# Moway_IR.net
KiCad netlist of a schematic drawn in Altium Designer
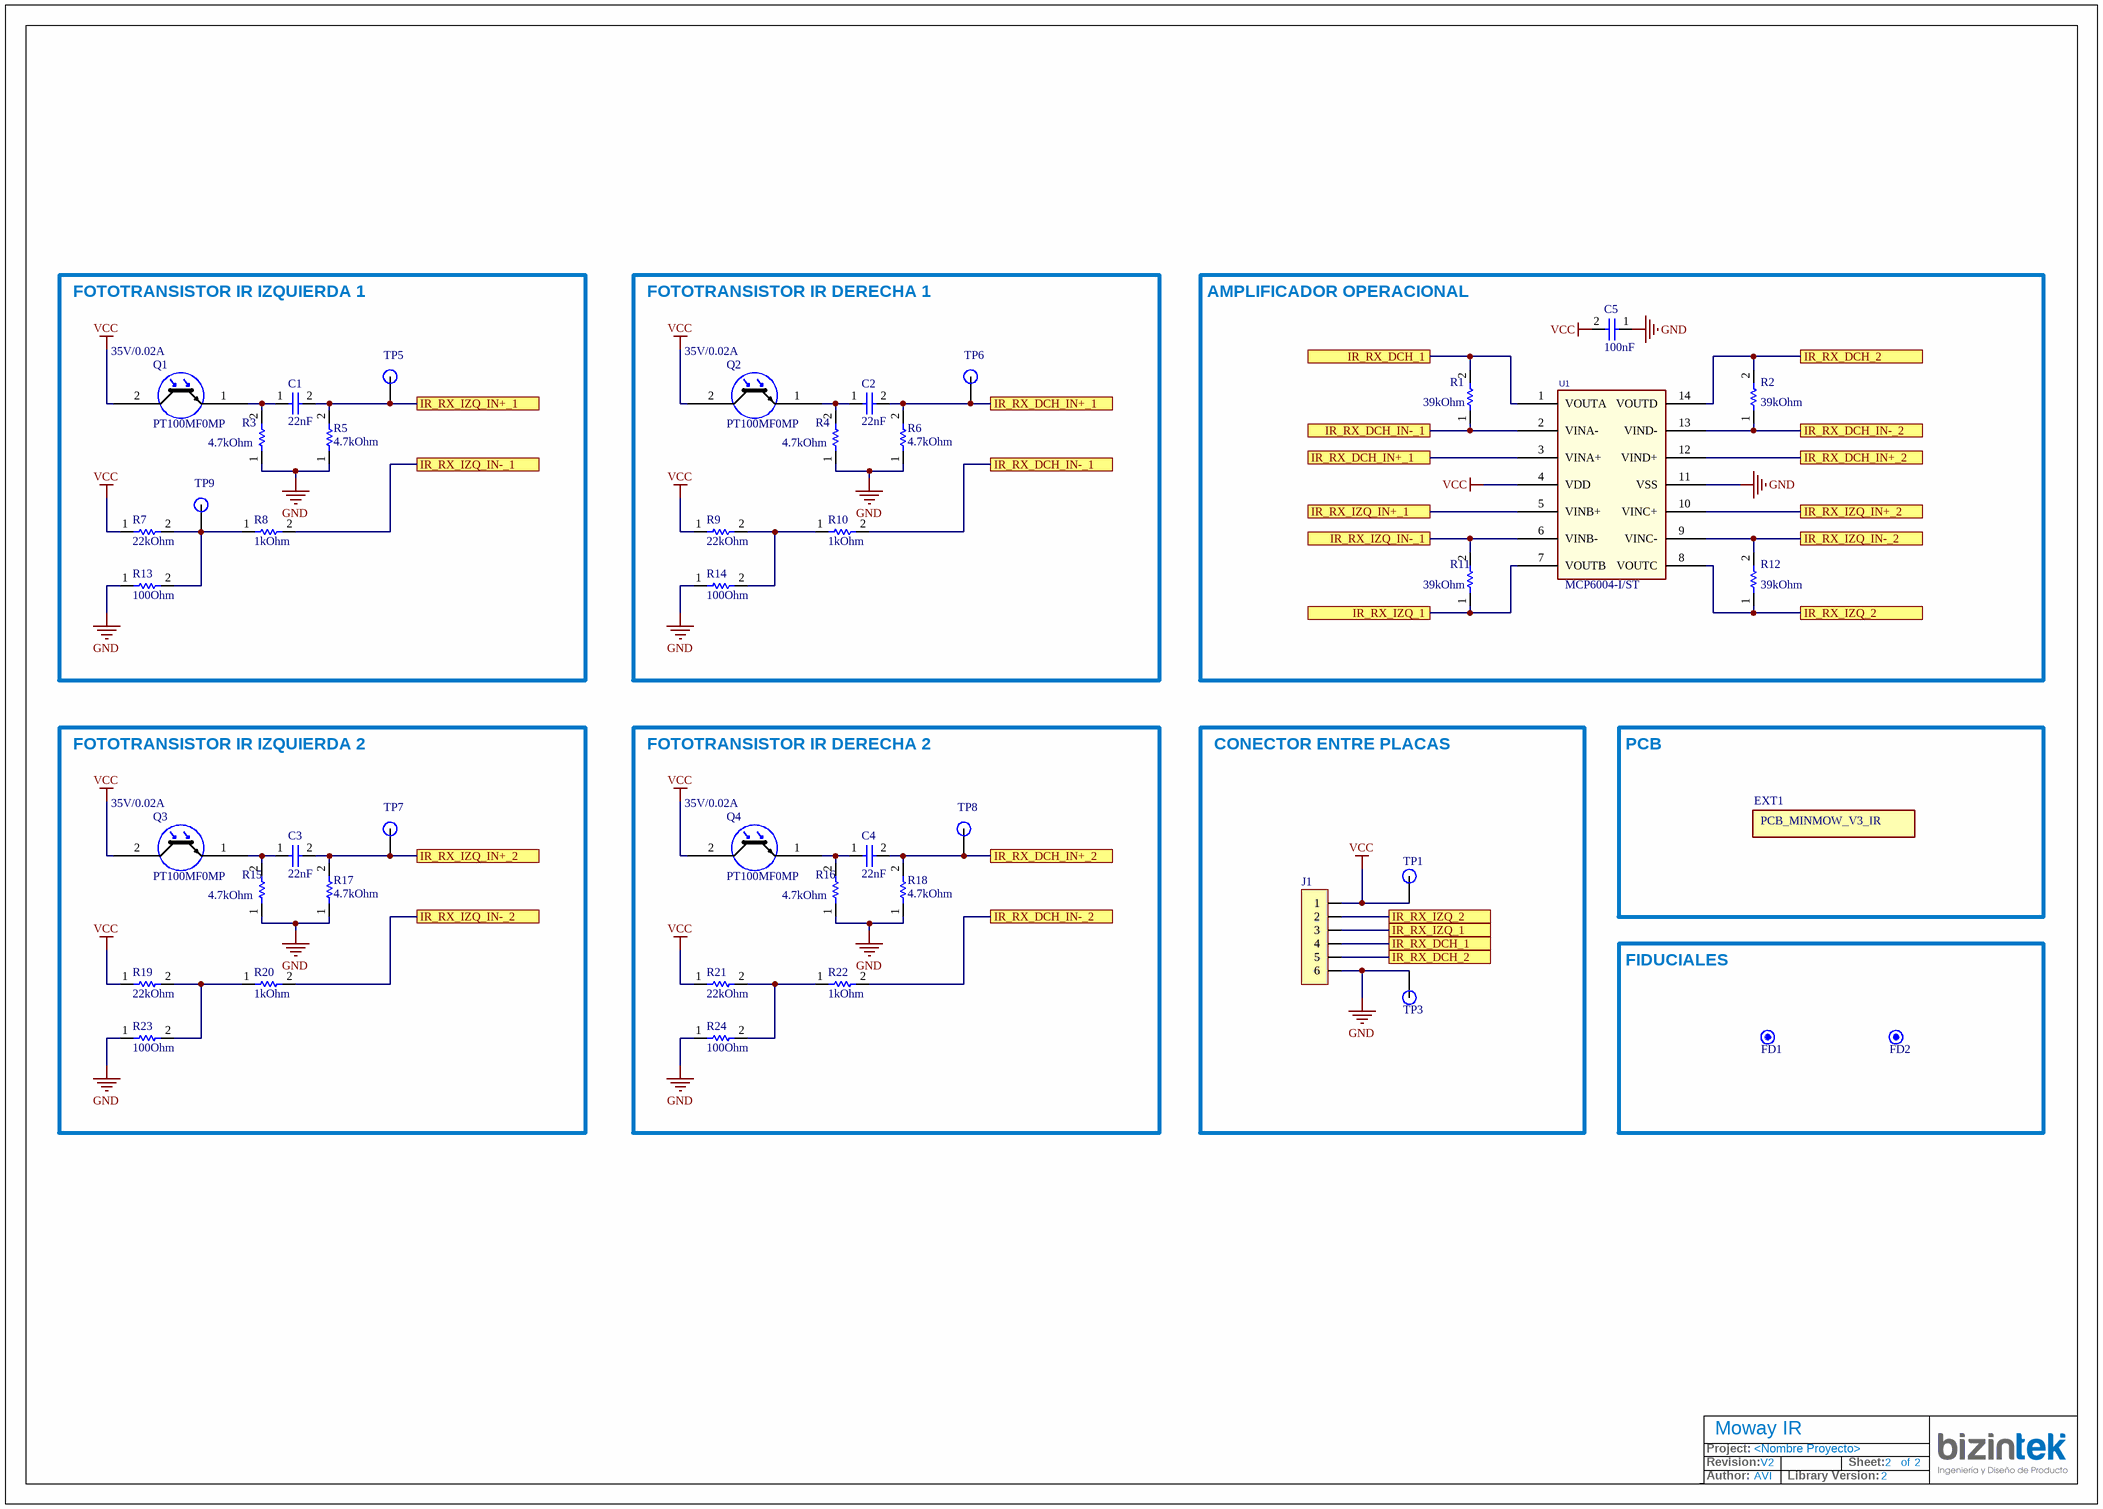
[diagram p0: Moway IR.SchDoc]

(export (version "E")
  (design (tool "Eeschema 10.0.6"))
  (components
    (comp (ref "C1")
      (value "22nF")
      (footprint "C0603")
      (description "CAPACITOR SMD 0603, 22nF , 10V, X7R")
      (fields (field (name "PART NUMBER") "C22NV10X7R0603") (field (name "VOLTAGE") "10"))
      (libsource (lib "BZI_ALTIUMLIB") (part "CAPACITOR"))
    )
    (comp (ref "C2")
      (value "22nF")
      (footprint "C0603")
      (description "CAPACITOR SMD 0603, 22nF , 10V, X7R")
      (fields (field (name "PART NUMBER") "C22NV10X7R0603") (field (name "VOLTAGE") "10"))
      (libsource (lib "BZI_ALTIUMLIB") (part "CAPACITOR"))
    )
    (comp (ref "C3")
      (value "22nF")
      (footprint "C0603")
      (description "CAPACITOR SMD 0603, 22nF , 10V, X7R")
      (fields (field (name "PART NUMBER") "C22NV10X7R0603") (field (name "VOLTAGE") "10"))
      (libsource (lib "BZI_ALTIUMLIB") (part "CAPACITOR"))
    )
    (comp (ref "C4")
      (value "22nF")
      (footprint "C0603")
      (description "CAPACITOR SMD 0603, 22nF , 10V, X7R")
      (fields (field (name "PART NUMBER") "C22NV10X7R0603") (field (name "VOLTAGE") "10"))
      (libsource (lib "BZI_ALTIUMLIB") (part "CAPACITOR"))
    )
    (comp (ref "C5")
      (value "100nF")
      (footprint "C0603")
      (description "CAPACITOR SMD 0603, 100nF, 10V, X7R")
      (fields (field (name "PART NUMBER") "C100NV10X7R0603") (field (name "VOLTAGE") "10"))
      (libsource (lib "BZI_ALTIUMLIB") (part "CAPACITOR"))
    )
    (comp (ref "EXT1")
      (value "PCB_MINMOW_V3_IR")
      (fields
        (field (name "PART NUMBER") "PCB")
        (field (name "MANUFACTURER") "BIZINTEK")
        (field (name "MANUFACTURER PART NUMBER") "PCB_MINMOW_V2_IR")
      )
      (libsource (lib "BZI_ALTIUMLIB") (part "EXTERNAL_GEN"))
    )
    (comp (ref "FD1")
      (value "FIDUCIAL")
      (footprint "FIDUCIAL")
      (libsource (lib "BZI_ALTIUMLIB") (part "FIDUCIAL"))
    )
    (comp (ref "FD2")
      (value "FIDUCIAL")
      (footprint "FIDUCIAL")
      (libsource (lib "BZI_ALTIUMLIB") (part "FIDUCIAL"))
    )
    (comp (ref "J1")
      (value "PAD_6PIN_3X2_1.05MM_1.27MM_PITCH")
      (footprint "PAD_6PIN_3X2_1.05MM_1.27MM_PITCH")
      (libsource (lib "BZI_ALTIUMLIB") (part "HEADER_6PIN"))
    )
    (comp (ref "Q1")
      (value "35V/0.02A")
      (footprint "PT100MF0MP_SIDE")
      (description "SMT Phototransistor, 15º angle, 910nm, 3.45mA (SIDE MOUNTING)")
      (fields
        (field (name "PART NUMBER") "PT100MF0MP_S")
        (field (name "MANUFACTURER PART NUMBER") "PT100MF0MP")
        (field (name "MANUFACTURER") "SHARP")
      )
      (libsource (lib "BZI_ALTIUMLIB") (part "PHOTOTRANSISTOR_BJT"))
    )
    (comp (ref "Q2")
      (value "35V/0.02A")
      (footprint "PT100MF0MP_SIDE")
      (description "SMT Phototransistor, 15º angle, 910nm, 3.45mA (SIDE MOUNTING)")
      (fields
        (field (name "PART NUMBER") "PT100MF0MP_S")
        (field (name "MANUFACTURER PART NUMBER") "PT100MF0MP")
        (field (name "MANUFACTURER") "SHARP")
      )
      (libsource (lib "BZI_ALTIUMLIB") (part "PHOTOTRANSISTOR_BJT"))
    )
    (comp (ref "Q3")
      (value "35V/0.02A")
      (footprint "PT100MF0MP_SIDE")
      (description "SMT Phototransistor, 15º angle, 910nm, 3.45mA (SIDE MOUNTING)")
      (fields
        (field (name "PART NUMBER") "PT100MF0MP_S")
        (field (name "MANUFACTURER PART NUMBER") "PT100MF0MP")
        (field (name "MANUFACTURER") "SHARP")
      )
      (libsource (lib "BZI_ALTIUMLIB") (part "PHOTOTRANSISTOR_BJT"))
    )
    (comp (ref "Q4")
      (value "35V/0.02A")
      (footprint "PT100MF0MP_SIDE")
      (description "SMT Phototransistor, 15º angle, 910nm, 3.45mA (SIDE MOUNTING)")
      (fields
        (field (name "PART NUMBER") "PT100MF0MP_S")
        (field (name "MANUFACTURER PART NUMBER") "PT100MF0MP")
        (field (name "MANUFACTURER") "SHARP")
      )
      (libsource (lib "BZI_ALTIUMLIB") (part "PHOTOTRANSISTOR_BJT"))
    )
    (comp (ref "R1")
      (value "39kOhm")
      (footprint "R0402")
      (description "RESISTOR SMD 0402, 39kOhm, 1%")
      (fields (field (name "PART NUMBER") "R39KT10402") (field (name "TOLERANCE") "1"))
      (libsource (lib "BZI_ALTIUMLIB") (part "RESISTOR"))
    )
    (comp (ref "R2")
      (value "39kOhm")
      (footprint "R0402")
      (description "RESISTOR SMD 0402, 39kOhm, 1%")
      (fields (field (name "PART NUMBER") "R39KT10402") (field (name "TOLERANCE") "1"))
      (libsource (lib "BZI_ALTIUMLIB") (part "RESISTOR"))
    )
    (comp (ref "R3")
      (value "4.7kOhm")
      (footprint "R0402")
      (description "RESISTOR SMD 0402, 4.7kOhm, 1%")
      (fields (field (name "PART NUMBER") "R4K7T10402") (field (name "TOLERANCE") "1"))
      (libsource (lib "BZI_ALTIUMLIB") (part "RESISTOR"))
    )
    (comp (ref "R4")
      (value "4.7kOhm")
      (footprint "R0402")
      (description "RESISTOR SMD 0402, 4.7kOhm, 1%")
      (fields (field (name "PART NUMBER") "R4K7T10402") (field (name "TOLERANCE") "1"))
      (libsource (lib "BZI_ALTIUMLIB") (part "RESISTOR"))
    )
    (comp (ref "R5")
      (value "4.7kOhm")
      (footprint "R0402")
      (description "RESISTOR SMD 0402, 4.7kOhm, 1%")
      (fields (field (name "PART NUMBER") "R4K7T10402") (field (name "TOLERANCE") "1"))
      (libsource (lib "BZI_ALTIUMLIB") (part "RESISTOR"))
    )
    (comp (ref "R6")
      (value "4.7kOhm")
      (footprint "R0402")
      (description "RESISTOR SMD 0402, 4.7kOhm, 1%")
      (fields (field (name "PART NUMBER") "R4K7T10402") (field (name "TOLERANCE") "1"))
      (libsource (lib "BZI_ALTIUMLIB") (part "RESISTOR"))
    )
    (comp (ref "R7")
      (value "22kOhm")
      (footprint "R0402")
      (description "RESISTOR SMD 0402, 22kOhm, 1%")
      (fields (field (name "PART NUMBER") "R22KT10402") (field (name "TOLERANCE") "1"))
      (libsource (lib "BZI_ALTIUMLIB") (part "RESISTOR"))
    )
    (comp (ref "R8")
      (value "1kOhm")
      (footprint "R0402")
      (description "RESISTOR SMD 0402, 1kOhm, 1%")
      (fields (field (name "PART NUMBER") "R1KT10402") (field (name "TOLERANCE") "1"))
      (libsource (lib "BZI_ALTIUMLIB") (part "RESISTOR"))
    )
    (comp (ref "R9")
      (value "22kOhm")
      (footprint "R0402")
      (description "RESISTOR SMD 0402, 22kOhm, 1%")
      (fields (field (name "PART NUMBER") "R22KT10402") (field (name "TOLERANCE") "1"))
      (libsource (lib "BZI_ALTIUMLIB") (part "RESISTOR"))
    )
    (comp (ref "R10")
      (value "1kOhm")
      (footprint "R0402")
      (description "RESISTOR SMD 0402, 1kOhm, 1%")
      (fields (field (name "PART NUMBER") "R1KT10402") (field (name "TOLERANCE") "1"))
      (libsource (lib "BZI_ALTIUMLIB") (part "RESISTOR"))
    )
    (comp (ref "R11")
      (value "39kOhm")
      (footprint "R0402")
      (description "RESISTOR SMD 0402, 39kOhm, 1%")
      (fields (field (name "PART NUMBER") "R39KT10402") (field (name "TOLERANCE") "1"))
      (libsource (lib "BZI_ALTIUMLIB") (part "RESISTOR"))
    )
    (comp (ref "R12")
      (value "39kOhm")
      (footprint "R0402")
      (description "RESISTOR SMD 0402, 39kOhm, 1%")
      (fields (field (name "PART NUMBER") "R39KT10402") (field (name "TOLERANCE") "1"))
      (libsource (lib "BZI_ALTIUMLIB") (part "RESISTOR"))
    )
    (comp (ref "R13")
      (value "100Ohm")
      (footprint "R0402")
      (description "RESISTOR SMD 0402, 100Ohm, 1%")
      (fields (field (name "PART NUMBER") "R100T10402") (field (name "TOLERANCE") "1"))
      (libsource (lib "BZI_ALTIUMLIB") (part "RESISTOR"))
    )
    (comp (ref "R14")
      (value "100Ohm")
      (footprint "R0402")
      (description "RESISTOR SMD 0402, 100Ohm, 1%")
      (fields (field (name "PART NUMBER") "R100T10402") (field (name "TOLERANCE") "1"))
      (libsource (lib "BZI_ALTIUMLIB") (part "RESISTOR"))
    )
    (comp (ref "R15")
      (value "4.7kOhm")
      (footprint "R0402")
      (description "RESISTOR SMD 0402, 4.7kOhm, 1%")
      (fields (field (name "PART NUMBER") "R4K7T10402") (field (name "TOLERANCE") "1"))
      (libsource (lib "BZI_ALTIUMLIB") (part "RESISTOR"))
    )
    (comp (ref "R16")
      (value "4.7kOhm")
      (footprint "R0402")
      (description "RESISTOR SMD 0402, 4.7kOhm, 1%")
      (fields (field (name "PART NUMBER") "R4K7T10402") (field (name "TOLERANCE") "1"))
      (libsource (lib "BZI_ALTIUMLIB") (part "RESISTOR"))
    )
    (comp (ref "R17")
      (value "4.7kOhm")
      (footprint "R0402")
      (description "RESISTOR SMD 0402, 4.7kOhm, 1%")
      (fields (field (name "PART NUMBER") "R4K7T10402") (field (name "TOLERANCE") "1"))
      (libsource (lib "BZI_ALTIUMLIB") (part "RESISTOR"))
    )
    (comp (ref "R18")
      (value "4.7kOhm")
      (footprint "R0402")
      (description "RESISTOR SMD 0402, 4.7kOhm, 1%")
      (fields (field (name "PART NUMBER") "R4K7T10402") (field (name "TOLERANCE") "1"))
      (libsource (lib "BZI_ALTIUMLIB") (part "RESISTOR"))
    )
    (comp (ref "R19")
      (value "22kOhm")
      (footprint "R0402")
      (description "RESISTOR SMD 0402, 22kOhm, 1%")
      (fields (field (name "PART NUMBER") "R22KT10402") (field (name "TOLERANCE") "1"))
      (libsource (lib "BZI_ALTIUMLIB") (part "RESISTOR"))
    )
    (comp (ref "R20")
      (value "1kOhm")
      (footprint "R0402")
      (description "RESISTOR SMD 0402, 1kOhm, 1%")
      (fields (field (name "PART NUMBER") "R1KT10402") (field (name "TOLERANCE") "1"))
      (libsource (lib "BZI_ALTIUMLIB") (part "RESISTOR"))
    )
    (comp (ref "R21")
      (value "22kOhm")
      (footprint "R0402")
      (description "RESISTOR SMD 0402, 22kOhm, 1%")
      (fields (field (name "PART NUMBER") "R22KT10402") (field (name "TOLERANCE") "1"))
      (libsource (lib "BZI_ALTIUMLIB") (part "RESISTOR"))
    )
    (comp (ref "R22")
      (value "1kOhm")
      (footprint "R0402")
      (description "RESISTOR SMD 0402, 1kOhm, 1%")
      (fields (field (name "PART NUMBER") "R1KT10402") (field (name "TOLERANCE") "1"))
      (libsource (lib "BZI_ALTIUMLIB") (part "RESISTOR"))
    )
    (comp (ref "R23")
      (value "100Ohm")
      (footprint "R0402")
      (description "RESISTOR SMD 0402, 100Ohm, 1%")
      (fields (field (name "PART NUMBER") "R100T10402") (field (name "TOLERANCE") "1"))
      (libsource (lib "BZI_ALTIUMLIB") (part "RESISTOR"))
    )
    (comp (ref "R24")
      (value "100Ohm")
      (footprint "R0402")
      (description "RESISTOR SMD 0402, 100Ohm, 1%")
      (fields (field (name "PART NUMBER") "R100T10402") (field (name "TOLERANCE") "1"))
      (libsource (lib "BZI_ALTIUMLIB") (part "RESISTOR"))
    )
    (comp (ref "TP1")
      (value "TEST_POINT_1MM")
      (footprint "TEST_POINT_1MM")
      (libsource (lib "BZI_ALTIUMLIB") (part "TEST_POINT"))
    )
    (comp (ref "TP3")
      (value "TEST_POINT_1MM")
      (footprint "TEST_POINT_1MM")
      (libsource (lib "BZI_ALTIUMLIB") (part "TEST_POINT"))
    )
    (comp (ref "TP5")
      (value "TEST_POINT_1MM")
      (footprint "TEST_POINT_1MM")
      (libsource (lib "BZI_ALTIUMLIB") (part "TEST_POINT"))
    )
    (comp (ref "TP6")
      (value "TEST_POINT_1MM")
      (footprint "TEST_POINT_1MM")
      (libsource (lib "BZI_ALTIUMLIB") (part "TEST_POINT"))
    )
    (comp (ref "TP7")
      (value "TEST_POINT_1MM")
      (footprint "TEST_POINT_1MM")
      (libsource (lib "BZI_ALTIUMLIB") (part "TEST_POINT"))
    )
    (comp (ref "TP8")
      (value "TEST_POINT_1MM")
      (footprint "TEST_POINT_1MM")
      (libsource (lib "BZI_ALTIUMLIB") (part "TEST_POINT"))
    )
    (comp (ref "TP9")
      (value "TEST_POINT_1MM")
      (footprint "TEST_POINT_1MM")
      (libsource (lib "BZI_ALTIUMLIB") (part "TEST_POINT"))
    )
    (comp (ref "U1")
      (value "MCP6004IST")
      (footprint "TSSOP14_MCP")
      (description "1MHz Low-Power Op Amp")
      (fields
        (field (name "MANUFACTURER PART NUMBER") "MCP6004-I/ST")
        (field (name "MANUFACTURER") "MICROCHIP")
      )
      (libsource (lib "BZI_ALTIUMLIB") (part "MCP6004IST"))
    )
  )
  (nets
    (net (code "1") (name "/IR_RX_DCH_1") (class "Default")
      (node (ref "J1") (pin "4") (pinfunction "4_4") (pintype "passive"))
      (node (ref "R1") (pin "2") (pinfunction "2_2") (pintype "passive"))
      (node (ref "U1") (pin "1") (pinfunction "VOUTA_1") (pintype "passive"))
    )
    (net (code "2") (name "/IR_RX_DCH_2") (class "Default")
      (node (ref "J1") (pin "5") (pinfunction "5_5") (pintype "passive"))
      (node (ref "R2") (pin "2") (pinfunction "2_2") (pintype "passive"))
      (node (ref "U1") (pin "14") (pinfunction "VOUTD_14") (pintype "passive"))
    )
    (net (code "3") (name "/IR_RX_DCH_IN+_1") (class "Default")
      (node (ref "C2") (pin "2") (pinfunction "2_2") (pintype "passive"))
      (node (ref "R6") (pin "2") (pinfunction "2_2") (pintype "passive"))
      (node (ref "TP6") (pin "1") (pinfunction "1_1") (pintype "passive"))
      (node (ref "U1") (pin "3") (pinfunction "VINA+_3") (pintype "passive"))
    )
    (net (code "4") (name "/IR_RX_DCH_IN+_2") (class "Default")
      (node (ref "C4") (pin "2") (pinfunction "2_2") (pintype "passive"))
      (node (ref "R18") (pin "2") (pinfunction "2_2") (pintype "passive"))
      (node (ref "TP8") (pin "1") (pinfunction "1_1") (pintype "passive"))
      (node (ref "U1") (pin "12") (pinfunction "VIND+_12") (pintype "passive"))
    )
    (net (code "5") (name "/IR_RX_DCH_IN-_1") (class "Default")
      (node (ref "R1") (pin "1") (pinfunction "1_1") (pintype "passive"))
      (node (ref "R10") (pin "2") (pinfunction "2_2") (pintype "passive"))
      (node (ref "U1") (pin "2") (pinfunction "VINA-_2") (pintype "passive"))
    )
    (net (code "6") (name "/IR_RX_DCH_IN-_2") (class "Default")
      (node (ref "R2") (pin "1") (pinfunction "1_1") (pintype "passive"))
      (node (ref "R22") (pin "2") (pinfunction "2_2") (pintype "passive"))
      (node (ref "U1") (pin "13") (pinfunction "VIND-_13") (pintype "passive"))
    )
    (net (code "7") (name "/IR_RX_IZQ_1") (class "Default")
      (node (ref "J1") (pin "3") (pinfunction "3_3") (pintype "passive"))
      (node (ref "R11") (pin "1") (pinfunction "1_1") (pintype "passive"))
      (node (ref "U1") (pin "7") (pinfunction "VOUTB_7") (pintype "passive"))
    )
    (net (code "8") (name "/IR_RX_IZQ_2") (class "Default")
      (node (ref "J1") (pin "2") (pinfunction "2_2") (pintype "passive"))
      (node (ref "R12") (pin "1") (pinfunction "1_1") (pintype "passive"))
      (node (ref "U1") (pin "8") (pinfunction "VOUTC_8") (pintype "passive"))
    )
    (net (code "9") (name "/IR_RX_IZQ_IN+_1") (class "Default")
      (node (ref "C1") (pin "2") (pinfunction "2_2") (pintype "passive"))
      (node (ref "R5") (pin "2") (pinfunction "2_2") (pintype "passive"))
      (node (ref "TP5") (pin "1") (pinfunction "1_1") (pintype "passive"))
      (node (ref "U1") (pin "5") (pinfunction "VINB+_5") (pintype "passive"))
    )
    (net (code "10") (name "/IR_RX_IZQ_IN+_2") (class "Default")
      (node (ref "C3") (pin "2") (pinfunction "2_2") (pintype "passive"))
      (node (ref "R17") (pin "2") (pinfunction "2_2") (pintype "passive"))
      (node (ref "TP7") (pin "1") (pinfunction "1_1") (pintype "passive"))
      (node (ref "U1") (pin "10") (pinfunction "VINC+_10") (pintype "passive"))
    )
    (net (code "11") (name "/IR_RX_IZQ_IN-_1") (class "Default")
      (node (ref "R11") (pin "2") (pinfunction "2_2") (pintype "passive"))
      (node (ref "R8") (pin "2") (pinfunction "2_2") (pintype "passive"))
      (node (ref "U1") (pin "6") (pinfunction "VINB-_6") (pintype "passive"))
    )
    (net (code "12") (name "/IR_RX_IZQ_IN-_2") (class "Default")
      (node (ref "R12") (pin "2") (pinfunction "2_2") (pintype "passive"))
      (node (ref "R20") (pin "2") (pinfunction "2_2") (pintype "passive"))
      (node (ref "U1") (pin "9") (pinfunction "VINC-_9") (pintype "passive"))
    )
    (net (code "13") (name "GND") (class "Default")
      (node (ref "C5") (pin "1") (pinfunction "1_1") (pintype "passive"))
      (node (ref "J1") (pin "6") (pinfunction "6_6") (pintype "passive"))
      (node (ref "R13") (pin "1") (pinfunction "1_1") (pintype "passive"))
      (node (ref "R14") (pin "1") (pinfunction "1_1") (pintype "passive"))
      (node (ref "R15") (pin "1") (pinfunction "1_1") (pintype "passive"))
      (node (ref "R16") (pin "1") (pinfunction "1_1") (pintype "passive"))
      (node (ref "R17") (pin "1") (pinfunction "1_1") (pintype "passive"))
      (node (ref "R18") (pin "1") (pinfunction "1_1") (pintype "passive"))
      (node (ref "R23") (pin "1") (pinfunction "1_1") (pintype "passive"))
      (node (ref "R24") (pin "1") (pinfunction "1_1") (pintype "passive"))
      (node (ref "R3") (pin "1") (pinfunction "1_1") (pintype "passive"))
      (node (ref "R4") (pin "1") (pinfunction "1_1") (pintype "passive"))
      (node (ref "R5") (pin "1") (pinfunction "1_1") (pintype "passive"))
      (node (ref "R6") (pin "1") (pinfunction "1_1") (pintype "passive"))
      (node (ref "TP3") (pin "1") (pinfunction "1_1") (pintype "passive"))
      (node (ref "U1") (pin "11") (pinfunction "VSS_11") (pintype "passive"))
    )
    (net (code "14") (name "Net-(C1-Pad1)") (class "Default")
      (node (ref "C1") (pin "1") (pinfunction "1_1") (pintype "passive"))
      (node (ref "Q1") (pin "1") (pinfunction "1_1") (pintype "passive"))
      (node (ref "R3") (pin "2") (pinfunction "2_2") (pintype "passive"))
    )
    (net (code "15") (name "Net-(C2-Pad1)") (class "Default")
      (node (ref "C2") (pin "1") (pinfunction "1_1") (pintype "passive"))
      (node (ref "Q2") (pin "1") (pinfunction "1_1") (pintype "passive"))
      (node (ref "R4") (pin "2") (pinfunction "2_2") (pintype "passive"))
    )
    (net (code "16") (name "Net-(C3-Pad1)") (class "Default")
      (node (ref "C3") (pin "1") (pinfunction "1_1") (pintype "passive"))
      (node (ref "Q3") (pin "1") (pinfunction "1_1") (pintype "passive"))
      (node (ref "R15") (pin "2") (pinfunction "2_2") (pintype "passive"))
    )
    (net (code "17") (name "Net-(C4-Pad1)") (class "Default")
      (node (ref "C4") (pin "1") (pinfunction "1_1") (pintype "passive"))
      (node (ref "Q4") (pin "1") (pinfunction "1_1") (pintype "passive"))
      (node (ref "R16") (pin "2") (pinfunction "2_2") (pintype "passive"))
    )
    (net (code "18") (name "Net-(R10-Pad1)") (class "Default")
      (node (ref "R10") (pin "1") (pinfunction "1_1") (pintype "passive"))
      (node (ref "R14") (pin "2") (pinfunction "2_2") (pintype "passive"))
      (node (ref "R9") (pin "2") (pinfunction "2_2") (pintype "passive"))
    )
    (net (code "19") (name "Net-(R13-Pad2)") (class "Default")
      (node (ref "R13") (pin "2") (pinfunction "2_2") (pintype "passive"))
      (node (ref "R7") (pin "2") (pinfunction "2_2") (pintype "passive"))
      (node (ref "R8") (pin "1") (pinfunction "1_1") (pintype "passive"))
      (node (ref "TP9") (pin "1") (pinfunction "1_1") (pintype "passive"))
    )
    (net (code "20") (name "Net-(R19-Pad2)") (class "Default")
      (node (ref "R19") (pin "2") (pinfunction "2_2") (pintype "passive"))
      (node (ref "R20") (pin "1") (pinfunction "1_1") (pintype "passive"))
      (node (ref "R23") (pin "2") (pinfunction "2_2") (pintype "passive"))
    )
    (net (code "21") (name "Net-(R21-Pad2)") (class "Default")
      (node (ref "R21") (pin "2") (pinfunction "2_2") (pintype "passive"))
      (node (ref "R22") (pin "1") (pinfunction "1_1") (pintype "passive"))
      (node (ref "R24") (pin "2") (pinfunction "2_2") (pintype "passive"))
    )
    (net (code "22") (name "VCC") (class "Default")
      (node (ref "C5") (pin "2") (pinfunction "2_2") (pintype "passive"))
      (node (ref "J1") (pin "1") (pinfunction "1_1") (pintype "passive"))
      (node (ref "Q1") (pin "2") (pinfunction "2_2") (pintype "passive"))
      (node (ref "Q2") (pin "2") (pinfunction "2_2") (pintype "passive"))
      (node (ref "Q3") (pin "2") (pinfunction "2_2") (pintype "passive"))
      (node (ref "Q4") (pin "2") (pinfunction "2_2") (pintype "passive"))
      (node (ref "R19") (pin "1") (pinfunction "1_1") (pintype "passive"))
      (node (ref "R21") (pin "1") (pinfunction "1_1") (pintype "passive"))
      (node (ref "R7") (pin "1") (pinfunction "1_1") (pintype "passive"))
      (node (ref "R9") (pin "1") (pinfunction "1_1") (pintype "passive"))
      (node (ref "TP1") (pin "1") (pinfunction "1_1") (pintype "passive"))
      (node (ref "U1") (pin "4") (pinfunction "VDD_4") (pintype "passive"))
    )
  )
)
